# Schematics.net
KiCad netlist of a schematic drawn in EAGLE
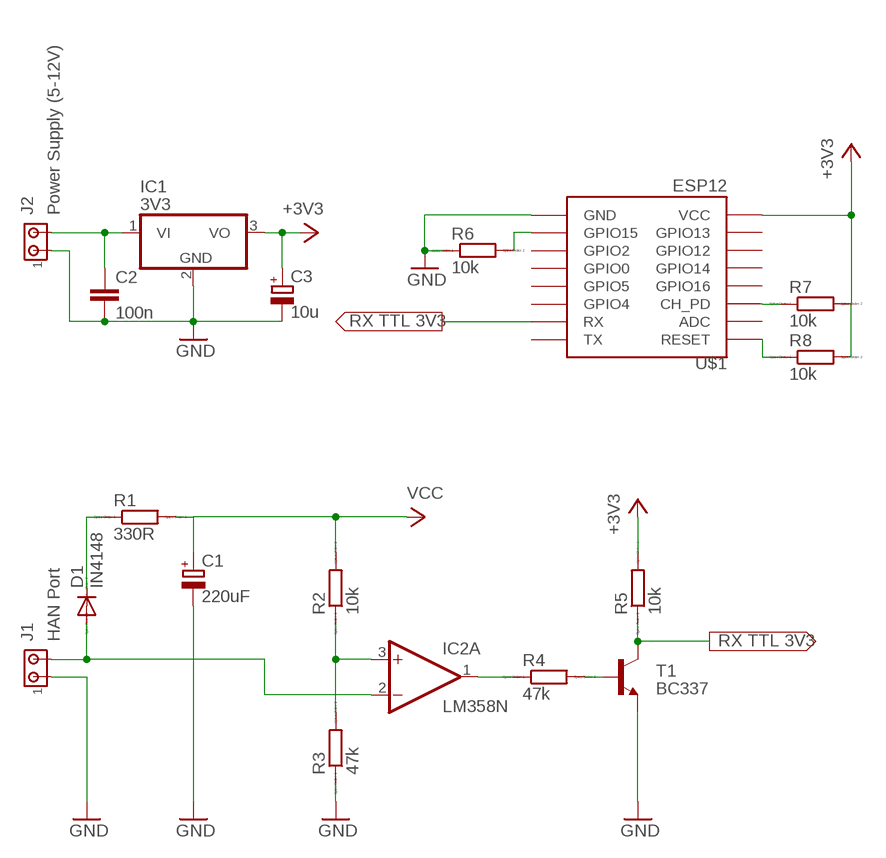
[diagram p0: schematic, sheet 1]

(export (version "E")
  (design (tool "Eeschema 10.0.6"))
  (components
    (comp (ref "C1")
      (value "220uF")
      (footprint "eagle-import:E3,5-10")
      (libsource (lib "eagle-import") (part "CPOL-EUE3.5-10"))
    )
    (comp (ref "C2")
      (value "100n")
      (footprint "eagle-import:C025-040X050")
      (libsource (lib "eagle-import") (part "C-EU025-040X050"))
    )
    (comp (ref "C3")
      (value "10u")
      (footprint "eagle-import:B45181A")
      (libsource (lib "eagle-import") (part "CPOL-EUB45181A"))
    )
    (comp (ref "D1")
      (value "IN4148")
      (footprint "eagle-import:DO35-7")
      (libsource (lib "eagle-import") (part "1N4148DO35-7"))
    )
    (comp (ref "IC1")
      (value "3V3")
      (footprint "eagle-import:TO220V")
      (libsource (lib "eagle-import") (part "78TV05"))
    )
    (comp (ref "IC2")
      (value "LM358N")
      (footprint "eagle-import:DIL08")
      (libsource (lib "eagle-import") (part "LM358N"))
    )
    (comp (ref "J1")
      (value "HAN Port")
      (footprint "eagle-import:1X2MTA")
      (libsource (lib "eagle-import") (part "MTA02-156"))
    )
    (comp (ref "J2")
      (value "Power Supply (5-12V)")
      (footprint "eagle-import:1X2MTA")
      (libsource (lib "eagle-import") (part "MTA02-156"))
    )
    (comp (ref "R1")
      (value "330R")
      (footprint "eagle-import:0207_10")
      (libsource (lib "eagle-import") (part "R0207/10"))
    )
    (comp (ref "R2")
      (value "10k")
      (footprint "eagle-import:0207_10")
      (libsource (lib "eagle-import") (part "R0207/10"))
    )
    (comp (ref "R3")
      (value "47k")
      (footprint "eagle-import:0207_10")
      (libsource (lib "eagle-import") (part "R0207/10"))
    )
    (comp (ref "R4")
      (value "47k")
      (footprint "eagle-import:0207_10")
      (libsource (lib "eagle-import") (part "R0207/10"))
    )
    (comp (ref "R5")
      (value "10k")
      (footprint "eagle-import:0207_10")
      (libsource (lib "eagle-import") (part "R0207/10"))
    )
    (comp (ref "R6")
      (value "10k")
      (footprint "eagle-import:0207_10")
      (libsource (lib "eagle-import") (part "R0207/10"))
    )
    (comp (ref "R7")
      (value "10k")
      (footprint "eagle-import:0207_10")
      (libsource (lib "eagle-import") (part "R0207/10"))
    )
    (comp (ref "R8")
      (value "10k")
      (footprint "eagle-import:0207_10")
      (libsource (lib "eagle-import") (part "R0207/10"))
    )
    (comp (ref "T1")
      (value "BC337")
      (footprint "eagle-import:TO92")
      (libsource (lib "eagle-import") (part "BC337"))
    )
    (comp (ref "U$1")
      (value "ESP12")
      (footprint "eagle-import:ESP12")
      (libsource (lib "eagle-import") (part "ESP12"))
    )
  )
  (nets
    (net (code "1") (name "+3V3") (class "Default")
      (node (ref "C3") (pin "+") (pinfunction "+_+") (pintype "passive"))
      (node (ref "IC1") (pin "3") (pinfunction "VO_3") (pintype "passive"))
      (node (ref "R5") (pin "2") (pinfunction "2_2") (pintype "passive"))
      (node (ref "R7") (pin "2") (pinfunction "2_2") (pintype "passive"))
      (node (ref "R8") (pin "2") (pinfunction "2_2") (pintype "passive"))
      (node (ref "U$1") (pin "VCC") (pinfunction "VCC_VCC") (pintype "bidirectional"))
    )
    (net (code "2") (name "GND") (class "Default")
      (node (ref "C1") (pin "-") (pinfunction "-_-") (pintype "passive"))
      (node (ref "C2") (pin "2") (pinfunction "2_2") (pintype "passive"))
      (node (ref "C3") (pin "-") (pinfunction "-_-") (pintype "passive"))
      (node (ref "IC1") (pin "2") (pinfunction "GND_2") (pintype "passive"))
      (node (ref "J1") (pin "1") (pinfunction "1_1") (pintype "passive"))
      (node (ref "J2") (pin "1") (pinfunction "1_1") (pintype "passive"))
      (node (ref "R3") (pin "1") (pinfunction "1_1") (pintype "passive"))
      (node (ref "R6") (pin "1") (pinfunction "1_1") (pintype "passive"))
      (node (ref "T1") (pin "1") (pinfunction "E_1") (pintype "passive"))
      (node (ref "U$1") (pin "GND") (pinfunction "GND_GND") (pintype "bidirectional"))
    )
    (net (code "3") (name "Net-(D1-PadC)") (class "Default")
      (node (ref "D1") (pin "C") (pinfunction "C_C") (pintype "passive"))
      (node (ref "R1") (pin "1") (pinfunction "1_1") (pintype "passive"))
    )
    (net (code "4") (name "Net-(IC1-VI)") (class "Default")
      (node (ref "C2") (pin "1") (pinfunction "1_1") (pintype "passive"))
      (node (ref "IC1") (pin "1") (pinfunction "VI_1") (pintype "input"))
      (node (ref "J2") (pin "2") (pinfunction "2_2") (pintype "passive"))
    )
    (net (code "5") (name "Net-(IC2A-+IN)") (class "Default")
      (node (ref "IC2") (pin "3") (pinfunction "+IN_3") (pintype "input"))
      (node (ref "R2") (pin "1") (pinfunction "1_1") (pintype "passive"))
      (node (ref "R3") (pin "2") (pinfunction "2_2") (pintype "passive"))
    )
    (net (code "6") (name "Net-(IC2A--IN)") (class "Default")
      (node (ref "D1") (pin "A") (pinfunction "A_A") (pintype "passive"))
      (node (ref "IC2") (pin "2") (pinfunction "-IN_2") (pintype "input"))
      (node (ref "J1") (pin "2") (pinfunction "2_2") (pintype "passive"))
    )
    (net (code "7") (name "Net-(IC2A-OUT)") (class "Default")
      (node (ref "IC2") (pin "1") (pinfunction "OUT_1") (pintype "output"))
      (node (ref "R4") (pin "1") (pinfunction "1_1") (pintype "passive"))
    )
    (net (code "8") (name "Net-(R6-Pad2)") (class "Default")
      (node (ref "R6") (pin "2") (pinfunction "2_2") (pintype "passive"))
      (node (ref "U$1") (pin "GPIO15") (pinfunction "GPIO15_GPIO15") (pintype "bidirectional"))
    )
    (net (code "9") (name "Net-(R7-Pad1)") (class "Default")
      (node (ref "R7") (pin "1") (pinfunction "1_1") (pintype "passive"))
      (node (ref "U$1") (pin "CH_PD") (pinfunction "CH_PD_CH_PD") (pintype "bidirectional"))
    )
    (net (code "10") (name "Net-(R8-Pad1)") (class "Default")
      (node (ref "R8") (pin "1") (pinfunction "1_1") (pintype "passive"))
      (node (ref "U$1") (pin "RESET") (pinfunction "RESET_RESET") (pintype "bidirectional"))
    )
    (net (code "11") (name "Net-(T1-B)") (class "Default")
      (node (ref "R4") (pin "2") (pinfunction "2_2") (pintype "passive"))
      (node (ref "T1") (pin "2") (pinfunction "B_2") (pintype "passive"))
    )
    (net (code "12") (name "Net-(T1-C)") (class "Default")
      (node (ref "R5") (pin "1") (pinfunction "1_1") (pintype "passive"))
      (node (ref "T1") (pin "3") (pinfunction "C_3") (pintype "passive"))
    )
    (net (code "13") (name "VCC") (class "Default")
      (node (ref "C1") (pin "+") (pinfunction "+_+") (pintype "passive"))
      (node (ref "R1") (pin "2") (pinfunction "2_2") (pintype "passive"))
      (node (ref "R2") (pin "2") (pinfunction "2_2") (pintype "passive"))
    )
    (net (code "14") (name "unconnected-(U$1-PadADC)") (class "Default")
      (node (ref "U$1") (pin "ADC") (pinfunction "ADC_ADC") (pintype "bidirectional"))
    )
    (net (code "15") (name "unconnected-(U$1-PadGPIO0)") (class "Default")
      (node (ref "U$1") (pin "GPIO0") (pinfunction "GPIO0_GPIO0") (pintype "bidirectional"))
    )
    (net (code "16") (name "unconnected-(U$1-PadGPIO2)") (class "Default")
      (node (ref "U$1") (pin "GPIO2") (pinfunction "GPIO2_GPIO2") (pintype "bidirectional"))
    )
    (net (code "17") (name "unconnected-(U$1-PadGPIO4)") (class "Default")
      (node (ref "U$1") (pin "GPIO4") (pinfunction "GPIO4_GPIO4") (pintype "bidirectional"))
    )
    (net (code "18") (name "unconnected-(U$1-PadGPIO5)") (class "Default")
      (node (ref "U$1") (pin "GPIO5") (pinfunction "GPIO5_GPIO5") (pintype "bidirectional"))
    )
    (net (code "19") (name "unconnected-(U$1-PadGPIO12)") (class "Default")
      (node (ref "U$1") (pin "GPIO12") (pinfunction "GPIO12_GPIO12") (pintype "bidirectional"))
    )
    (net (code "20") (name "unconnected-(U$1-PadGPIO13)") (class "Default")
      (node (ref "U$1") (pin "GPIO13") (pinfunction "GPIO13_GPIO13") (pintype "bidirectional"))
    )
    (net (code "21") (name "unconnected-(U$1-PadGPIO14)") (class "Default")
      (node (ref "U$1") (pin "GPIO14") (pinfunction "GPIO14_GPIO14") (pintype "bidirectional"))
    )
    (net (code "22") (name "unconnected-(U$1-PadGPIO16)") (class "Default")
      (node (ref "U$1") (pin "GPIO16") (pinfunction "GPIO16_GPIO16") (pintype "bidirectional"))
    )
    (net (code "23") (name "unconnected-(U$1-PadRX)") (class "Default")
      (node (ref "U$1") (pin "RX") (pinfunction "RX_RX") (pintype "bidirectional"))
    )
    (net (code "24") (name "unconnected-(U$1-PadTX)") (class "Default")
      (node (ref "U$1") (pin "TX") (pinfunction "TX_TX") (pintype "bidirectional"))
    )
  )
)
